# SCH_BMS_2023-06-01.net
KiCad netlist of a schematic drawn in EasyEDA
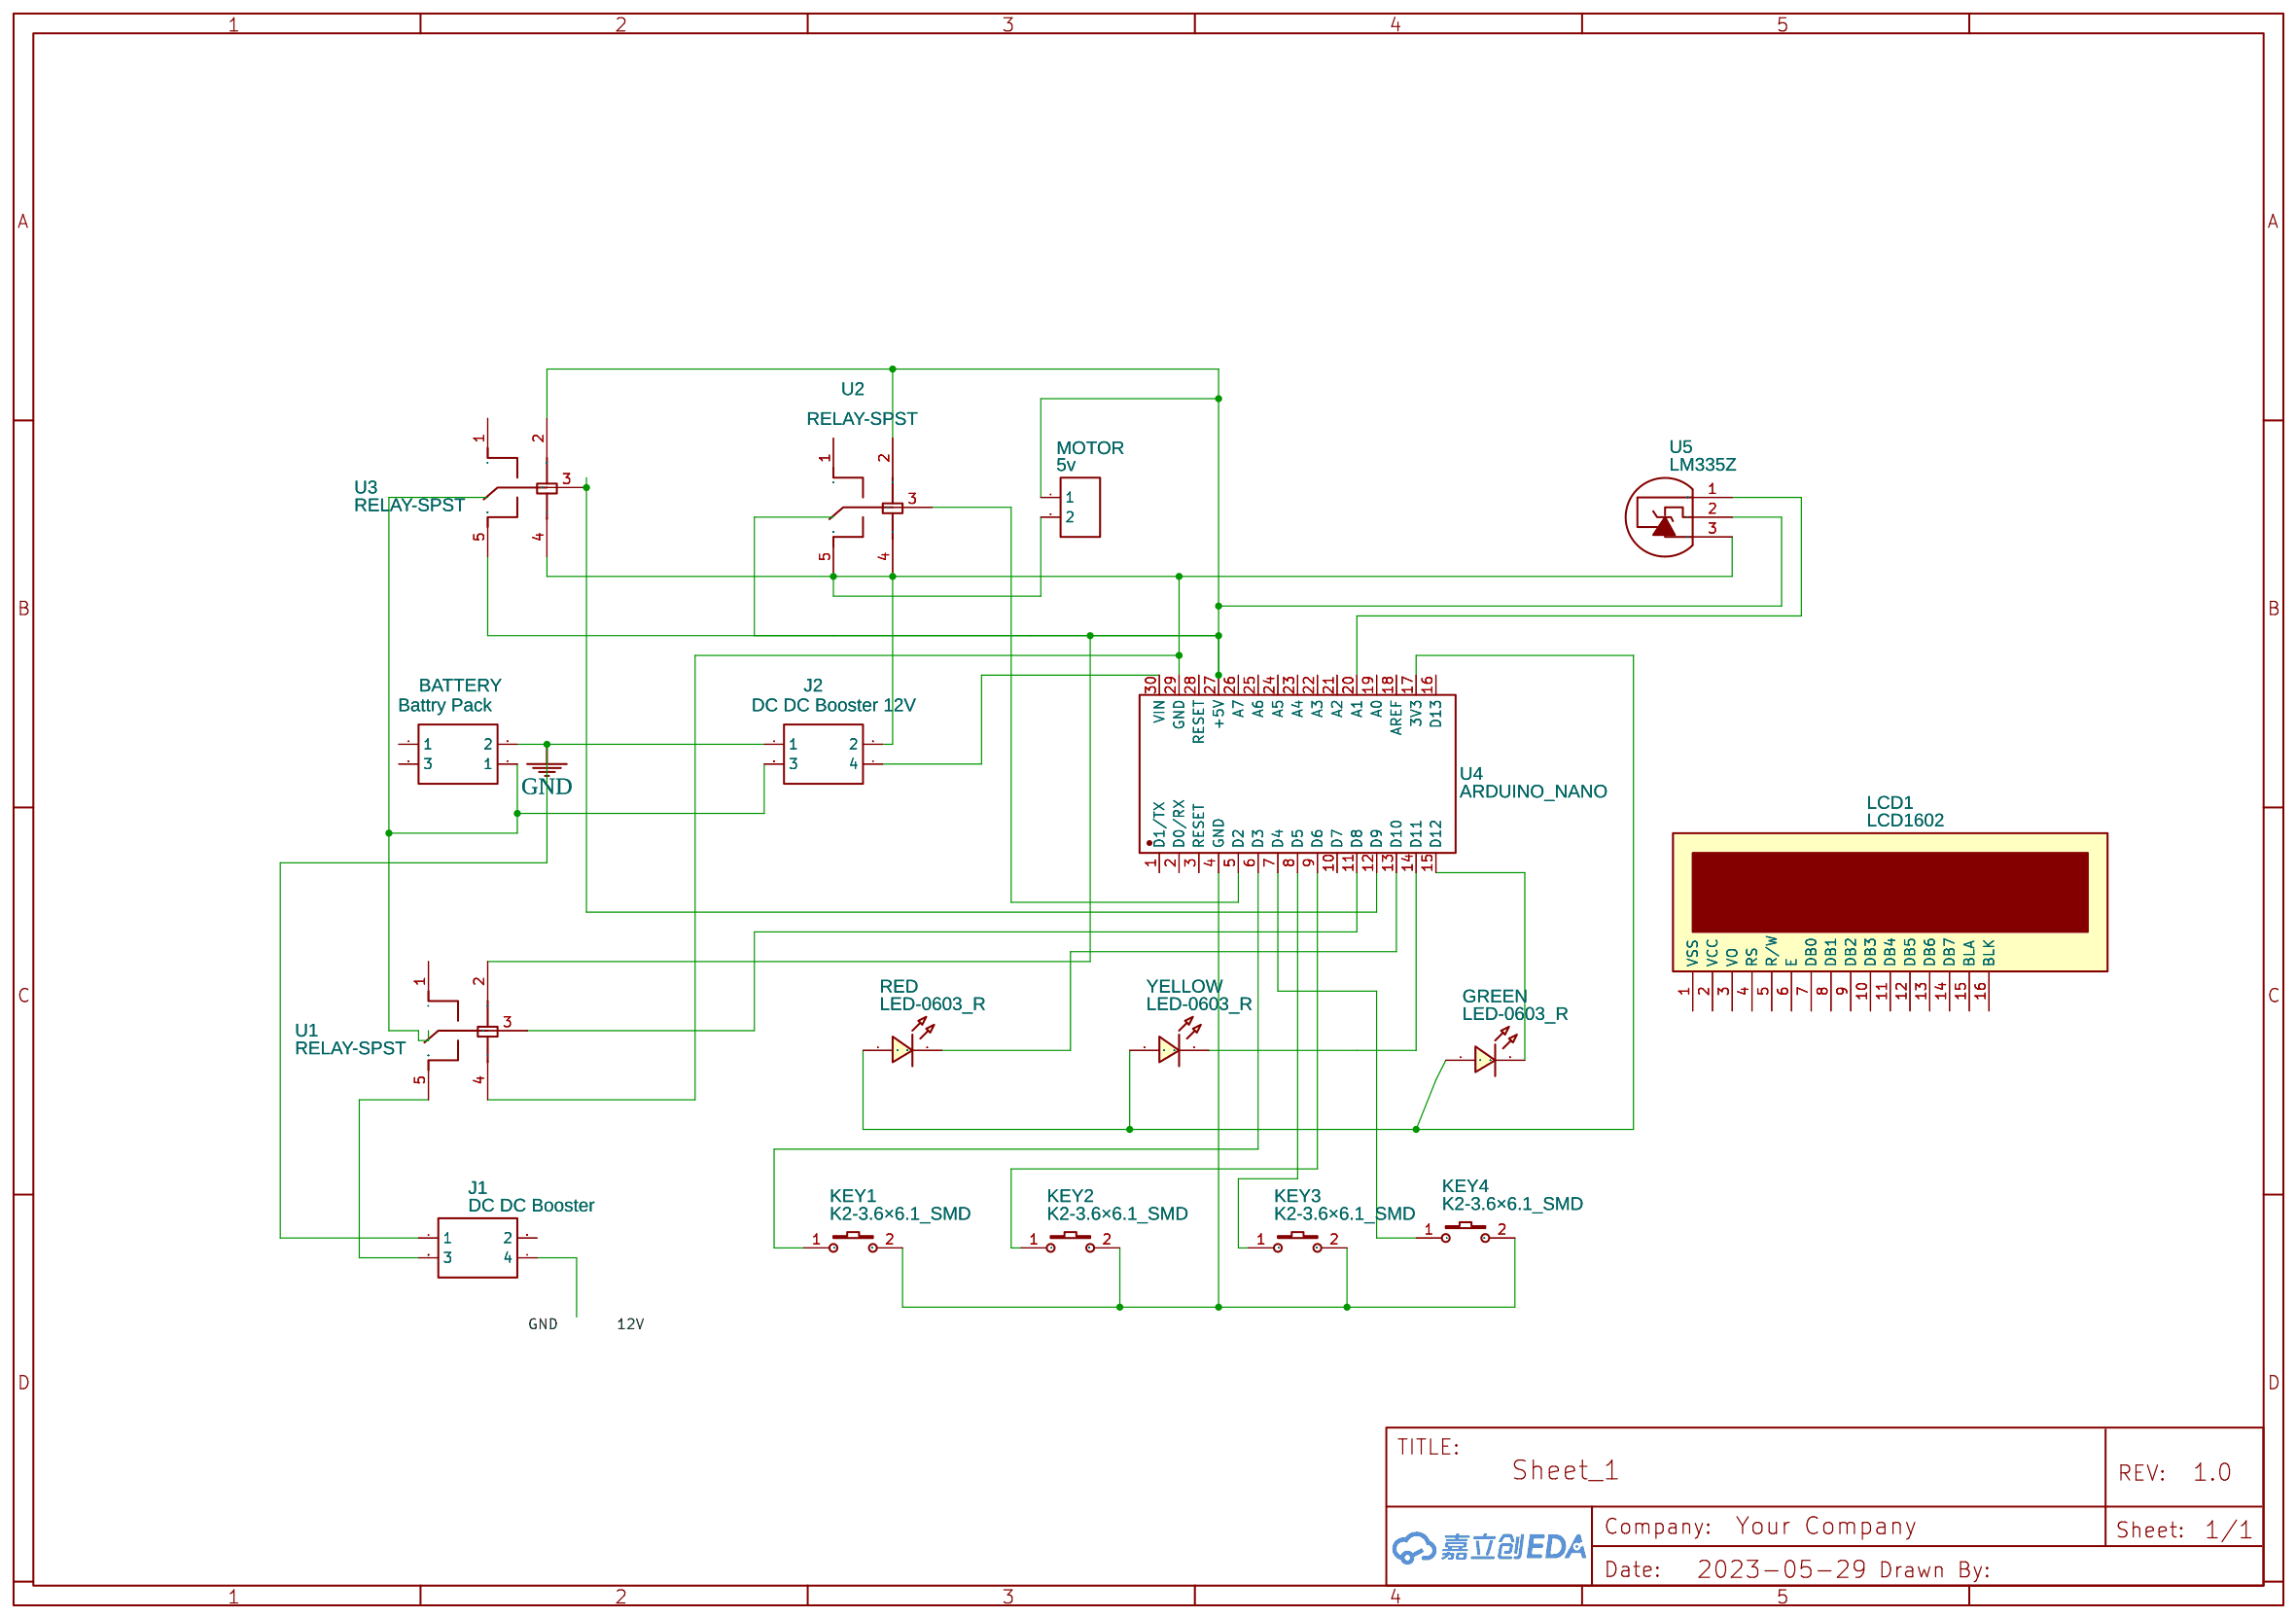
[diagram p0: schematic sheet]

(export (version "E")
  (design (tool "Eeschema 10.0.6"))
  (components
    (comp (ref "BATTERY")
      (value "Battry Pack")
      (fields (field (name "BOM_Supplier Part") "C239342"))
      (libsource (lib "") (part "HDR-F-2.54_2x2"))
    )
    (comp (ref "GREEN")
      (value "LED-0603_R")
      (fields
        (field (name "BOM_Manufacturer Part") "19-217/R6C-AL1M2VY/3T")
        (field (name "BOM_Supplier Part") "C72044")
      )
      (libsource (lib "") (part "LED-0603_R_1"))
    )
    (comp (ref "J1")
      (value "DC DC Booster")
      (fields (field (name "BOM_Supplier Part") "C66690"))
      (libsource (lib "") (part "HDR-M-2.54_2x2"))
    )
    (comp (ref "J2")
      (value "DC DC Booster 12V")
      (fields (field (name "BOM_Supplier Part") "C66690"))
      (libsource (lib "") (part "HDR-M-2.54_2x2"))
    )
    (comp (ref "KEY1")
      (value "K2-3.6×6.1_SMD")
      (fields
        (field (name "BOM_Manufacturer Part") "K2-1107ST-A4SW-06")
        (field (name "BOM_Supplier Part") "C118141")
      )
      (libsource (lib "") (part "K2-3.6×6.1_SMD"))
    )
    (comp (ref "KEY2")
      (value "K2-3.6×6.1_SMD")
      (fields
        (field (name "BOM_Manufacturer Part") "K2-1107ST-A4SW-06")
        (field (name "BOM_Supplier Part") "C118141")
      )
      (libsource (lib "") (part "K2-3.6×6.1_SMD"))
    )
    (comp (ref "KEY3")
      (value "K2-3.6×6.1_SMD")
      (fields
        (field (name "BOM_Manufacturer Part") "K2-1107ST-A4SW-06")
        (field (name "BOM_Supplier Part") "C118141")
      )
      (libsource (lib "") (part "K2-3.6×6.1_SMD"))
    )
    (comp (ref "KEY4")
      (value "K2-3.6×6.1_SMD")
      (fields
        (field (name "BOM_Manufacturer Part") "K2-1107ST-A4SW-06")
        (field (name "BOM_Supplier Part") "C118141")
      )
      (libsource (lib "") (part "K2-3.6×6.1_SMD"))
    )
    (comp (ref "LCD1")
      (value "LCD1602")
      (fields
        (field (name "BOM_Manufacturer Part") "LCM1602K-NSW-BBW")
        (field (name "BOM_Supplier Part") "C83275")
      )
      (libsource (lib "") (part "LCD1602"))
    )
    (comp (ref "MOTOR")
      (value "5v")
      (fields (field (name "BOM_Supplier Part") "C49661"))
      (libsource (lib "") (part "HDR-F-2.54_1x2"))
    )
    (comp (ref "RED")
      (value "LED-0603_R")
      (fields
        (field (name "BOM_Manufacturer Part") "19-217/R6C-AL1M2VY/3T")
        (field (name "BOM_Supplier Part") "C72044")
      )
      (libsource (lib "") (part "LED-0603_R_2"))
    )
    (comp (ref "U1")
      (value "RELAY-SPST")
      (fields
        (field (name "BOM_Manufacturer Part") "Relay-SPST")
        (field (name "BOM_Supplier Part") "C2941249")
      )
      (libsource (lib "") (part "RELAY-SPST"))
    )
    (comp (ref "U2")
      (value "RELAY-SPST")
      (fields
        (field (name "BOM_Manufacturer Part") "Relay-SPST")
        (field (name "BOM_Supplier Part") "C2941249")
      )
      (libsource (lib "") (part "RELAY-SPST"))
    )
    (comp (ref "U3")
      (value "RELAY-SPST")
      (fields
        (field (name "BOM_Manufacturer Part") "Relay-SPST")
        (field (name "BOM_Supplier Part") "C2941249")
      )
      (libsource (lib "") (part "RELAY-SPST"))
    )
    (comp (ref "U4")
      (value "ARDUINO_NANO")
      (fields (field (name "BOM_Supplier Part") "C9900017879"))
      (libsource (lib "") (part "ARDUINO_NANO"))
    )
    (comp (ref "U5")
      (value "LM335Z")
      (fields (field (name "BOM_Supplier Part") "C10629"))
      (libsource (lib "") (part "LM335Z"))
    )
    (comp (ref "YELLOW")
      (value "LED-0603_R")
      (fields
        (field (name "BOM_Manufacturer Part") "19-217/R6C-AL1M2VY/3T")
        (field (name "BOM_Supplier Part") "C72044")
      )
      (libsource (lib "") (part "LED-0603_R"))
    )
  )
  (nets
    (net (code "2") (name "GND") (class "Default")
      (node (ref "BATTERY") (pin "2") (pinfunction "2_2") (pintype "unspecified"))
      (node (ref "J1") (pin "1") (pinfunction "1_1") (pintype "input"))
      (node (ref "J2") (pin "1") (pinfunction "1_1") (pintype "input"))
    )
    (net (code "3") (name "Net-(BATTERY-Pad1)_1") (class "Default")
      (node (ref "BATTERY") (pin "1") (pinfunction "1_1") (pintype "unspecified"))
      (node (ref "J2") (pin "3") (pinfunction "3_3") (pintype "input"))
    )
    (net (code "4") (name "Net-(J1-Pad3)") (class "Default")
      (node (ref "J1") (pin "3") (pinfunction "3_3") (pintype "input"))
      (node (ref "U1") (pin "5") (pinfunction "5_5") (pintype "unspecified"))
    )
    (net (code "5") (name "Net-(KEY1-Pad2)") (class "Default")
      (node (ref "KEY1") (pin "2") (pinfunction "2_2") (pintype "unspecified"))
      (node (ref "KEY2") (pin "2") (pinfunction "2_2") (pintype "unspecified"))
      (node (ref "KEY3") (pin "2") (pinfunction "2_2") (pintype "unspecified"))
      (node (ref "KEY4") (pin "2") (pinfunction "2_2") (pintype "unspecified"))
      (node (ref "U4") (pin "4") (pinfunction "GND_4") (pintype "unspecified"))
    )
    (net (code "6") (name "Net-(U4-+5V)") (class "Default")
      (node (ref "MOTOR") (pin "1") (pinfunction "1_1") (pintype "input"))
      (node (ref "U1") (pin "2") (pinfunction "2_2") (pintype "unspecified"))
      (node (ref "U2") (pin "2") (pinfunction "2_2") (pintype "unspecified"))
      (node (ref "U3") (pin "2") (pinfunction "2_2") (pintype "unspecified"))
      (node (ref "U3") (pin "5") (pinfunction "5_5") (pintype "unspecified"))
      (node (ref "U4") (pin "27") (pinfunction "+5V_27") (pintype "unspecified"))
      (node (ref "U5") (pin "2") (pinfunction "V+_2") (pintype "unspecified"))
    )
    (net (code "7") (name "Net-(U4-3V3)") (class "Default")
      (node (ref "GREEN") (pin "1") (pinfunction "1_1") (pintype "unspecified"))
      (node (ref "RED") (pin "1") (pinfunction "1_1") (pintype "unspecified"))
      (node (ref "U4") (pin "17") (pinfunction "3V3_17") (pintype "unspecified"))
      (node (ref "YELLOW") (pin "1") (pinfunction "1_1") (pintype "unspecified"))
    )
    (net (code "8") (name "Net-(U4-A1)") (class "Default")
      (node (ref "U4") (pin "20") (pinfunction "A1_20") (pintype "unspecified"))
      (node (ref "U5") (pin "1") (pinfunction "ADJ_1") (pintype "unspecified"))
    )
    (net (code "9") (name "Net-(U4-D2)") (class "Default")
      (node (ref "U2") (pin "3") (pinfunction "3_3") (pintype "unspecified"))
      (node (ref "U4") (pin "5") (pinfunction "D2_5") (pintype "unspecified"))
    )
    (net (code "10") (name "Net-(U4-D3)") (class "Default")
      (node (ref "KEY1") (pin "1") (pinfunction "1_1") (pintype "unspecified"))
      (node (ref "U4") (pin "6") (pinfunction "D3_6") (pintype "unspecified"))
    )
    (net (code "11") (name "Net-(U4-D4)") (class "Default")
      (node (ref "KEY4") (pin "1") (pinfunction "1_1") (pintype "unspecified"))
      (node (ref "U4") (pin "7") (pinfunction "D4_7") (pintype "unspecified"))
    )
    (net (code "12") (name "Net-(U4-D5)") (class "Default")
      (node (ref "KEY3") (pin "1") (pinfunction "1_1") (pintype "unspecified"))
      (node (ref "U4") (pin "8") (pinfunction "D5_8") (pintype "unspecified"))
    )
    (net (code "13") (name "Net-(U4-D6)") (class "Default")
      (node (ref "KEY2") (pin "1") (pinfunction "1_1") (pintype "unspecified"))
      (node (ref "U4") (pin "9") (pinfunction "D6_9") (pintype "unspecified"))
    )
    (net (code "14") (name "Net-(U4-D8)") (class "Default")
      (node (ref "U1") (pin "3") (pinfunction "3_3") (pintype "unspecified"))
      (node (ref "U4") (pin "11") (pinfunction "D8_11") (pintype "unspecified"))
    )
    (net (code "15") (name "Net-(U4-D9)") (class "Default")
      (node (ref "U3") (pin "3") (pinfunction "3_3") (pintype "unspecified"))
      (node (ref "U4") (pin "12") (pinfunction "D9_12") (pintype "unspecified"))
    )
    (net (code "16") (name "Net-(U4-D10)") (class "Default")
      (node (ref "RED") (pin "2") (pinfunction "2_2") (pintype "unspecified"))
      (node (ref "U4") (pin "13") (pinfunction "D10_13") (pintype "unspecified"))
    )
    (net (code "17") (name "Net-(U4-D11)") (class "Default")
      (node (ref "U4") (pin "14") (pinfunction "D11_14") (pintype "unspecified"))
      (node (ref "YELLOW") (pin "2") (pinfunction "2_2") (pintype "unspecified"))
    )
    (net (code "18") (name "Net-(U4-D12)") (class "Default")
      (node (ref "GREEN") (pin "2") (pinfunction "2_2") (pintype "unspecified"))
      (node (ref "U4") (pin "15") (pinfunction "D12_15") (pintype "unspecified"))
    )
    (net (code "19") (name "Net-(U4-VIN)") (class "Default")
      (node (ref "J2") (pin "4") (pinfunction "4_4") (pintype "input"))
      (node (ref "U4") (pin "30") (pinfunction "VIN_30") (pintype "unspecified"))
    )
    (net (code "20") (name "Net-(U5-V-)") (class "Default")
      (node (ref "J2") (pin "2") (pinfunction "2_2") (pintype "input"))
      (node (ref "MOTOR") (pin "2") (pinfunction "2_2") (pintype "input"))
      (node (ref "U1") (pin "4") (pinfunction "4_4") (pintype "unspecified"))
      (node (ref "U2") (pin "4") (pinfunction "4_4") (pintype "unspecified"))
      (node (ref "U2") (pin "5") (pinfunction "5_5") (pintype "unspecified"))
      (node (ref "U3") (pin "4") (pinfunction "4_4") (pintype "unspecified"))
      (node (ref "U4") (pin "29") (pinfunction "GND_29") (pintype "unspecified"))
      (node (ref "U5") (pin "3") (pinfunction "V-_3") (pintype "unspecified"))
    )
    (net (code "21") (name "unconnected-(BATTERY-Pad1)") (class "Default")
      (node (ref "BATTERY") (pin "1") (pinfunction "1_1") (pintype "unspecified"))
    )
    (net (code "22") (name "unconnected-(BATTERY-Pad3)") (class "Default")
      (node (ref "BATTERY") (pin "3") (pinfunction "3_3") (pintype "unspecified"))
    )
    (net (code "23") (name "unconnected-(J1-Pad2)") (class "Default")
      (node (ref "J1") (pin "2") (pinfunction "2_2") (pintype "input"))
    )
    (net (code "24") (name "unconnected-(J1-Pad4)") (class "Default")
      (node (ref "J1") (pin "4") (pinfunction "4_4") (pintype "input"))
    )
    (net (code "25") (name "unconnected-(LCD1-BLA-Pad15)") (class "Default")
      (node (ref "LCD1") (pin "15") (pinfunction "BLA_15") (pintype "unspecified"))
    )
    (net (code "26") (name "unconnected-(LCD1-BLK-Pad16)") (class "Default")
      (node (ref "LCD1") (pin "16") (pinfunction "BLK_16") (pintype "unspecified"))
    )
    (net (code "27") (name "unconnected-(LCD1-DB0-Pad7)") (class "Default")
      (node (ref "LCD1") (pin "7") (pinfunction "DB0_7") (pintype "unspecified"))
    )
    (net (code "28") (name "unconnected-(LCD1-DB1-Pad8)") (class "Default")
      (node (ref "LCD1") (pin "8") (pinfunction "DB1_8") (pintype "unspecified"))
    )
    (net (code "29") (name "unconnected-(LCD1-DB2-Pad9)") (class "Default")
      (node (ref "LCD1") (pin "9") (pinfunction "DB2_9") (pintype "unspecified"))
    )
    (net (code "30") (name "unconnected-(LCD1-DB3-Pad10)") (class "Default")
      (node (ref "LCD1") (pin "10") (pinfunction "DB3_10") (pintype "unspecified"))
    )
    (net (code "31") (name "unconnected-(LCD1-DB4-Pad11)") (class "Default")
      (node (ref "LCD1") (pin "11") (pinfunction "DB4_11") (pintype "unspecified"))
    )
    (net (code "32") (name "unconnected-(LCD1-DB5-Pad12)") (class "Default")
      (node (ref "LCD1") (pin "12") (pinfunction "DB5_12") (pintype "unspecified"))
    )
    (net (code "33") (name "unconnected-(LCD1-DB6-Pad13)") (class "Default")
      (node (ref "LCD1") (pin "13") (pinfunction "DB6_13") (pintype "unspecified"))
    )
    (net (code "34") (name "unconnected-(LCD1-DB7-Pad14)") (class "Default")
      (node (ref "LCD1") (pin "14") (pinfunction "DB7_14") (pintype "unspecified"))
    )
    (net (code "35") (name "unconnected-(LCD1-E-Pad6)") (class "Default")
      (node (ref "LCD1") (pin "6") (pinfunction "E_6") (pintype "unspecified"))
    )
    (net (code "36") (name "unconnected-(LCD1-RS-Pad4)") (class "Default")
      (node (ref "LCD1") (pin "4") (pinfunction "RS_4") (pintype "unspecified"))
    )
    (net (code "37") (name "unconnected-(LCD1-R{slash}W-Pad5)") (class "Default")
      (node (ref "LCD1") (pin "5") (pinfunction "R/W_5") (pintype "unspecified"))
    )
    (net (code "38") (name "unconnected-(LCD1-VCC-Pad2)") (class "Default")
      (node (ref "LCD1") (pin "2") (pinfunction "VCC_2") (pintype "unspecified"))
    )
    (net (code "39") (name "unconnected-(LCD1-VO-Pad3)") (class "Default")
      (node (ref "LCD1") (pin "3") (pinfunction "VO_3") (pintype "unspecified"))
    )
    (net (code "40") (name "unconnected-(LCD1-VSS-Pad1)") (class "Default")
      (node (ref "LCD1") (pin "1") (pinfunction "VSS_1") (pintype "unspecified"))
    )
    (net (code "41") (name "unconnected-(U1-Pad1)") (class "Default")
      (node (ref "U1") (pin "1") (pinfunction "1_1") (pintype "unspecified"))
    )
    (net (code "42") (name "unconnected-(U2-Pad1)") (class "Default")
      (node (ref "U2") (pin "1") (pinfunction "1_1") (pintype "unspecified"))
    )
    (net (code "43") (name "unconnected-(U3-Pad1)") (class "Default")
      (node (ref "U3") (pin "1") (pinfunction "1_1") (pintype "unspecified"))
    )
    (net (code "44") (name "unconnected-(U4-A0-Pad19)") (class "Default")
      (node (ref "U4") (pin "19") (pinfunction "A0_19") (pintype "unspecified"))
    )
    (net (code "45") (name "unconnected-(U4-A2-Pad21)") (class "Default")
      (node (ref "U4") (pin "21") (pinfunction "A2_21") (pintype "unspecified"))
    )
    (net (code "46") (name "unconnected-(U4-A3-Pad22)") (class "Default")
      (node (ref "U4") (pin "22") (pinfunction "A3_22") (pintype "unspecified"))
    )
    (net (code "47") (name "unconnected-(U4-A4-Pad23)") (class "Default")
      (node (ref "U4") (pin "23") (pinfunction "A4_23") (pintype "unspecified"))
    )
    (net (code "48") (name "unconnected-(U4-A5-Pad24)") (class "Default")
      (node (ref "U4") (pin "24") (pinfunction "A5_24") (pintype "unspecified"))
    )
    (net (code "49") (name "unconnected-(U4-A6-Pad25)") (class "Default")
      (node (ref "U4") (pin "25") (pinfunction "A6_25") (pintype "unspecified"))
    )
    (net (code "50") (name "unconnected-(U4-A7-Pad26)") (class "Default")
      (node (ref "U4") (pin "26") (pinfunction "A7_26") (pintype "unspecified"))
    )
    (net (code "51") (name "unconnected-(U4-AREF-Pad18)") (class "Default")
      (node (ref "U4") (pin "18") (pinfunction "AREF_18") (pintype "unspecified"))
    )
    (net (code "52") (name "unconnected-(U4-D0{slash}RX-Pad2)") (class "Default")
      (node (ref "U4") (pin "2") (pinfunction "D0/RX_2") (pintype "unspecified"))
    )
    (net (code "53") (name "unconnected-(U4-D1{slash}TX-Pad1)") (class "Default")
      (node (ref "U4") (pin "1") (pinfunction "D1/TX_1") (pintype "unspecified"))
    )
    (net (code "54") (name "unconnected-(U4-D7-Pad10)") (class "Default")
      (node (ref "U4") (pin "10") (pinfunction "D7_10") (pintype "unspecified"))
    )
    (net (code "55") (name "unconnected-(U4-D13-Pad16)") (class "Default")
      (node (ref "U4") (pin "16") (pinfunction "D13_16") (pintype "unspecified"))
    )
    (net (code "56") (name "unconnected-(U4-RESET-Pad3)") (class "Default")
      (node (ref "U4") (pin "3") (pinfunction "RESET_3") (pintype "unspecified"))
    )
    (net (code "57") (name "unconnected-(U4-RESET-Pad28)") (class "Default")
      (node (ref "U4") (pin "28") (pinfunction "RESET_28") (pintype "unspecified"))
    )
  )
)
